# auxboxshield1_42.net
KiCad netlist of a schematic drawn in EAGLE
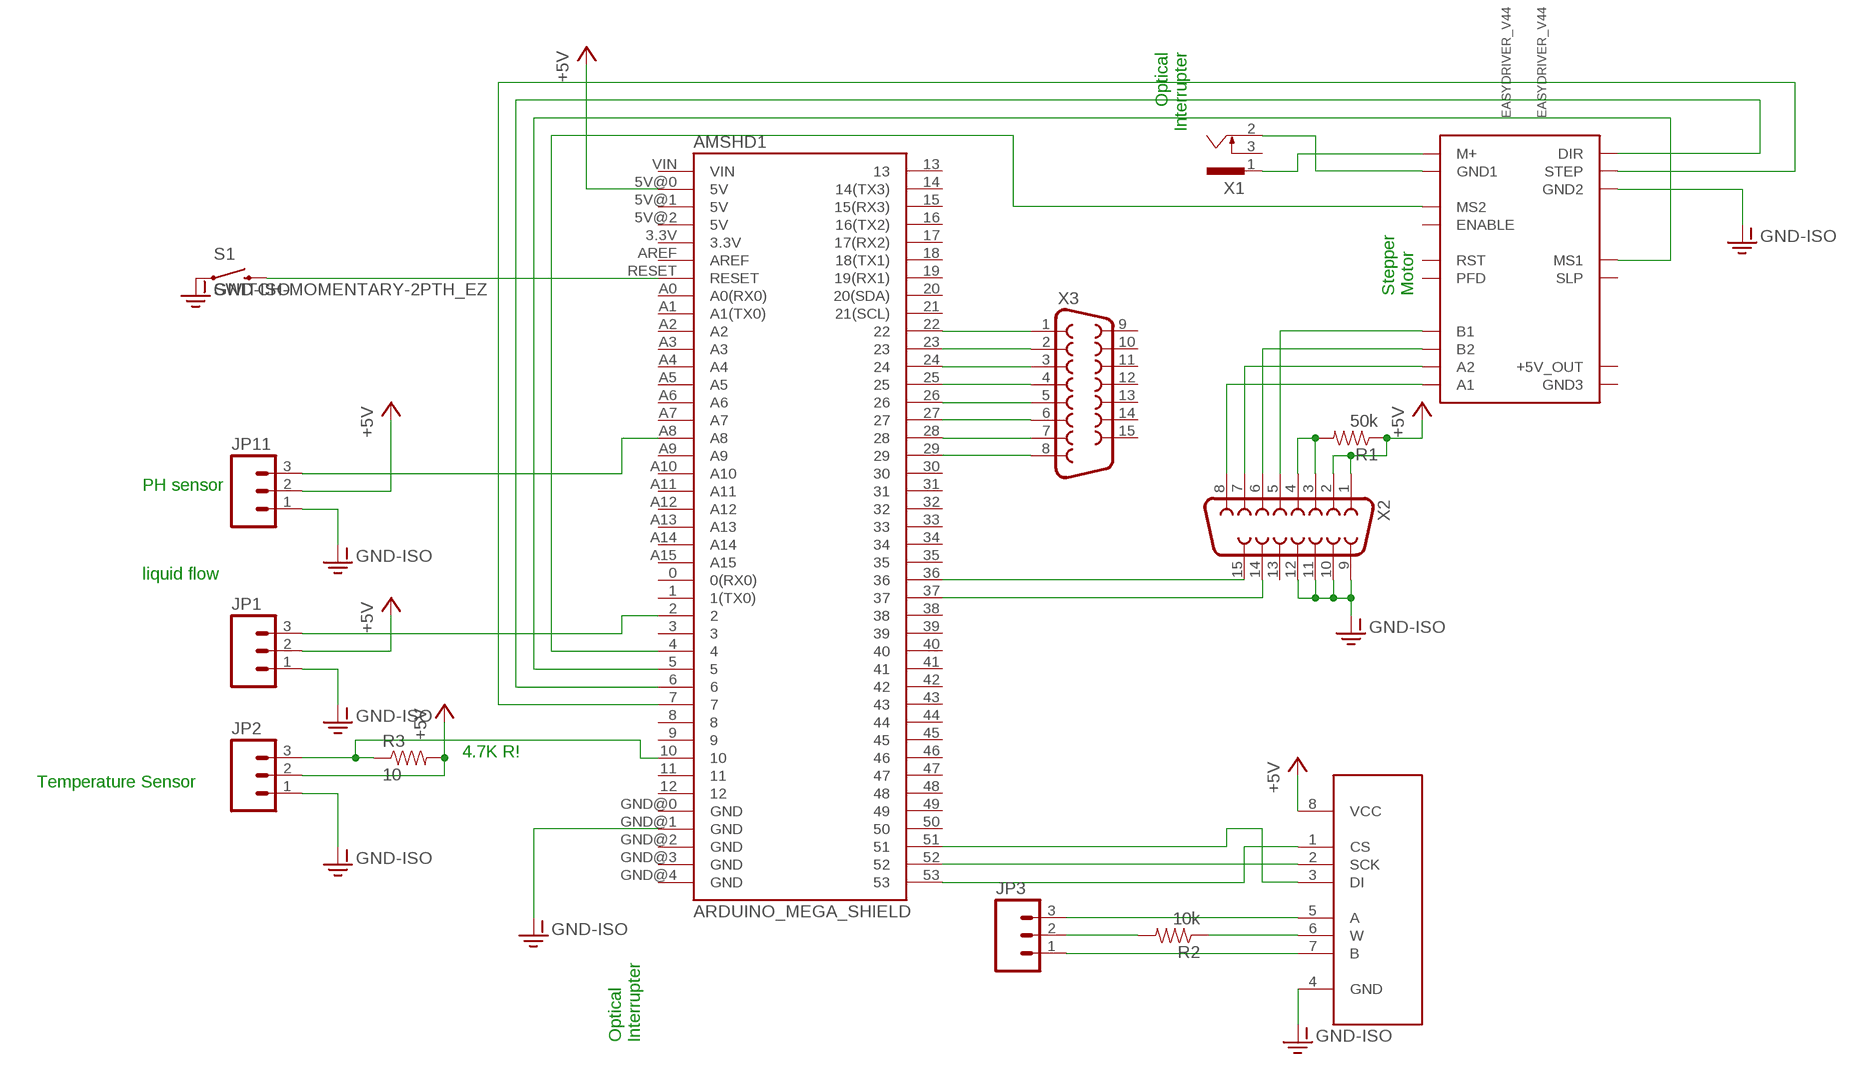
[diagram p0: schematic, sheet 1]

(export (version "E")
  (design (tool "Eeschema 10.0.6"))
  (components
    (comp (ref "AMSHD1")
      (value "ARDUINO_MEGA_SHIELD")
      (footprint "eagle-import:ARDUINO_MEGA_SHIELD")
      (libsource (lib "eagle-import") (part "ARDUINO_MEGA_SHIELD"))
    )
    (comp (ref "EASYDRIVER_V44")
      (value "EASYDRIVER_V44")
      (footprint "eagle-import:EASYDRIVER_V44")
      (libsource (lib "eagle-import") (part "EASYDRIVER_V44"))
    )
    (comp (ref "JP1")
      (value "M03POLAR")
      (footprint "eagle-import:MOLEX-1X3")
      (libsource (lib "eagle-import") (part "M03POLAR"))
    )
    (comp (ref "JP2")
      (value "M03POLAR")
      (footprint "eagle-import:MOLEX-1X3")
      (libsource (lib "eagle-import") (part "M03POLAR"))
    )
    (comp (ref "JP3")
      (value "M03POLAR")
      (footprint "eagle-import:MOLEX-1X3")
      (libsource (lib "eagle-import") (part "M03POLAR"))
    )
    (comp (ref "JP11")
      (value "M03POLAR")
      (footprint "eagle-import:MOLEX-1X3")
      (libsource (lib "eagle-import") (part "M03POLAR"))
    )
    (comp (ref "R1")
      (value "50k")
      (footprint "eagle-import:AXIAL-0.3")
      (libsource (lib "eagle-import") (part "100KOHM-1/4W-5%(PTH)"))
    )
    (comp (ref "R2")
      (value "10k")
      (footprint "eagle-import:AXIAL-0.3")
      (libsource (lib "eagle-import") (part "10KOHM-1/4W-1%(PTH)HORIZ"))
    )
    (comp (ref "R3")
      (value "10")
      (footprint "eagle-import:AXIAL-0.3")
      (libsource (lib "eagle-import") (part "10OHM-1/4W-5%(PTH)"))
    )
    (comp (ref "S1")
      (value "SWITCH-MOMENTARY-2PTH_EZ")
      (footprint "eagle-import:TACTILE-PTH-EZ")
      (libsource (lib "eagle-import") (part "SWITCH-MOMENTARY-2PTH_EZ"))
    )
    (comp (ref "U2")
      (value "MCP41XXXDIL")
      (footprint "eagle-import:DIL-08")
      (libsource (lib "eagle-import") (part "MCP41XXXDIL"))
    )
    (comp (ref "X1")
      (value "SCD-014A")
      (footprint "eagle-import:SCD-014-A")
      (libsource (lib "eagle-import") (part "SCD-014A"))
    )
    (comp (ref "X2")
      (value "F15HP")
      (footprint "eagle-import:F15HP")
      (libsource (lib "eagle-import") (part "F15HP"))
    )
    (comp (ref "X3")
      (value "F15HP")
      (footprint "eagle-import:F15HP")
      (libsource (lib "eagle-import") (part "F15HP"))
    )
  )
  (nets
    (net (code "1") (name "+5V") (class "Default")
      (node (ref "AMSHD1") (pin "5V@0") (pinfunction "5V_5V@0") (pintype "bidirectional"))
      (node (ref "JP1") (pin "2") (pinfunction "2_2") (pintype "passive"))
      (node (ref "JP11") (pin "2") (pinfunction "2_2") (pintype "passive"))
      (node (ref "JP2") (pin "2") (pinfunction "2_2") (pintype "passive"))
      (node (ref "R1") (pin "P$1") (pinfunction "1_P$1") (pintype "passive"))
      (node (ref "R3") (pin "P$2") (pinfunction "2_P$2") (pintype "passive"))
      (node (ref "U2") (pin "8") (pinfunction "VCC_8") (pintype "bidirectional"))
      (node (ref "X2") (pin "1") (pinfunction "1_1") (pintype "passive"))
      (node (ref "X2") (pin "2") (pinfunction "2_2") (pintype "passive"))
    )
    (net (code "2") (name "GND-ISO") (class "Default")
      (node (ref "AMSHD1") (pin "GND@1") (pinfunction "GND_GND@1") (pintype "bidirectional"))
      (node (ref "EASYDRIVER_V44") (pin "GND2") (pinfunction "GND2_GND2") (pintype "bidirectional"))
      (node (ref "JP1") (pin "1") (pinfunction "1_1") (pintype "passive"))
      (node (ref "JP11") (pin "1") (pinfunction "1_1") (pintype "passive"))
      (node (ref "JP2") (pin "1") (pinfunction "1_1") (pintype "passive"))
      (node (ref "S1") (pin "1") (pinfunction "1_1") (pintype "passive"))
      (node (ref "U2") (pin "4") (pinfunction "GND_4") (pintype "bidirectional"))
      (node (ref "X2") (pin "10") (pinfunction "10_10") (pintype "passive"))
      (node (ref "X2") (pin "11") (pinfunction "11_11") (pintype "passive"))
      (node (ref "X2") (pin "12") (pinfunction "12_12") (pintype "passive"))
      (node (ref "X2") (pin "9") (pinfunction "9_9") (pintype "passive"))
    )
    (net (code "3") (name "Net-(AMSHD1-Pad2)") (class "Default")
      (node (ref "AMSHD1") (pin "2") (pinfunction "2_2") (pintype "bidirectional"))
      (node (ref "JP1") (pin "3") (pinfunction "3_3") (pintype "passive"))
    )
    (net (code "4") (name "Net-(AMSHD1-Pad4)") (class "Default")
      (node (ref "AMSHD1") (pin "4") (pinfunction "4_4") (pintype "bidirectional"))
      (node (ref "EASYDRIVER_V44") (pin "MS2") (pinfunction "MS2_MS2") (pintype "bidirectional"))
    )
    (net (code "5") (name "Net-(AMSHD1-Pad5)") (class "Default")
      (node (ref "AMSHD1") (pin "5") (pinfunction "5_5") (pintype "bidirectional"))
      (node (ref "EASYDRIVER_V44") (pin "MS1") (pinfunction "MS1_MS1") (pintype "bidirectional"))
    )
    (net (code "6") (name "Net-(AMSHD1-Pad6)") (class "Default")
      (node (ref "AMSHD1") (pin "6") (pinfunction "6_6") (pintype "bidirectional"))
      (node (ref "EASYDRIVER_V44") (pin "DIR") (pinfunction "DIR_DIR") (pintype "bidirectional"))
    )
    (net (code "7") (name "Net-(AMSHD1-Pad7)") (class "Default")
      (node (ref "AMSHD1") (pin "7") (pinfunction "7_7") (pintype "bidirectional"))
      (node (ref "EASYDRIVER_V44") (pin "STEP") (pinfunction "STEP_STEP") (pintype "bidirectional"))
    )
    (net (code "8") (name "Net-(AMSHD1-Pad22)") (class "Default")
      (node (ref "AMSHD1") (pin "22") (pinfunction "22_22") (pintype "bidirectional"))
      (node (ref "X3") (pin "1") (pinfunction "1_1") (pintype "passive"))
    )
    (net (code "9") (name "Net-(AMSHD1-Pad23)") (class "Default")
      (node (ref "AMSHD1") (pin "23") (pinfunction "23_23") (pintype "bidirectional"))
      (node (ref "X3") (pin "2") (pinfunction "2_2") (pintype "passive"))
    )
    (net (code "10") (name "Net-(AMSHD1-Pad24)") (class "Default")
      (node (ref "AMSHD1") (pin "24") (pinfunction "24_24") (pintype "bidirectional"))
      (node (ref "X3") (pin "3") (pinfunction "3_3") (pintype "passive"))
    )
    (net (code "11") (name "Net-(AMSHD1-Pad25)") (class "Default")
      (node (ref "AMSHD1") (pin "25") (pinfunction "25_25") (pintype "bidirectional"))
      (node (ref "X3") (pin "4") (pinfunction "4_4") (pintype "passive"))
    )
    (net (code "12") (name "Net-(AMSHD1-Pad26)") (class "Default")
      (node (ref "AMSHD1") (pin "26") (pinfunction "26_26") (pintype "bidirectional"))
      (node (ref "X3") (pin "5") (pinfunction "5_5") (pintype "passive"))
    )
    (net (code "13") (name "Net-(AMSHD1-Pad27)") (class "Default")
      (node (ref "AMSHD1") (pin "27") (pinfunction "27_27") (pintype "bidirectional"))
      (node (ref "X3") (pin "6") (pinfunction "6_6") (pintype "passive"))
    )
    (net (code "14") (name "Net-(AMSHD1-Pad28)") (class "Default")
      (node (ref "AMSHD1") (pin "28") (pinfunction "28_28") (pintype "bidirectional"))
      (node (ref "X3") (pin "7") (pinfunction "7_7") (pintype "passive"))
    )
    (net (code "15") (name "Net-(AMSHD1-Pad29)") (class "Default")
      (node (ref "AMSHD1") (pin "29") (pinfunction "29_29") (pintype "bidirectional"))
      (node (ref "X3") (pin "8") (pinfunction "8_8") (pintype "passive"))
    )
    (net (code "16") (name "Net-(AMSHD1-Pad36)") (class "Default")
      (node (ref "AMSHD1") (pin "36") (pinfunction "36_36") (pintype "bidirectional"))
      (node (ref "X2") (pin "15") (pinfunction "15_15") (pintype "passive"))
    )
    (net (code "17") (name "Net-(AMSHD1-Pad37)") (class "Default")
      (node (ref "AMSHD1") (pin "37") (pinfunction "37_37") (pintype "bidirectional"))
      (node (ref "X2") (pin "14") (pinfunction "14_14") (pintype "passive"))
    )
    (net (code "18") (name "Net-(AMSHD1-PadA8)") (class "Default")
      (node (ref "AMSHD1") (pin "A8") (pinfunction "A8_A8") (pintype "bidirectional"))
      (node (ref "JP11") (pin "3") (pinfunction "3_3") (pintype "passive"))
    )
    (net (code "19") (name "Net-(EASYDRIVER_V44-PadA1)") (class "Default")
      (node (ref "EASYDRIVER_V44") (pin "A1") (pinfunction "A1_A1") (pintype "bidirectional"))
      (node (ref "X2") (pin "8") (pinfunction "8_8") (pintype "passive"))
    )
    (net (code "20") (name "Net-(EASYDRIVER_V44-PadA2)") (class "Default")
      (node (ref "EASYDRIVER_V44") (pin "A2") (pinfunction "A2_A2") (pintype "bidirectional"))
      (node (ref "X2") (pin "7") (pinfunction "7_7") (pintype "passive"))
    )
    (net (code "21") (name "Net-(EASYDRIVER_V44-PadB1)") (class "Default")
      (node (ref "EASYDRIVER_V44") (pin "B1") (pinfunction "B1_B1") (pintype "bidirectional"))
      (node (ref "X2") (pin "5") (pinfunction "5_5") (pintype "passive"))
    )
    (net (code "22") (name "Net-(EASYDRIVER_V44-PadB2)") (class "Default")
      (node (ref "EASYDRIVER_V44") (pin "B2") (pinfunction "B2_B2") (pintype "bidirectional"))
      (node (ref "X2") (pin "6") (pinfunction "6_6") (pintype "passive"))
    )
    (net (code "23") (name "Net-(EASYDRIVER_V44-PadGND1)") (class "Default")
      (node (ref "EASYDRIVER_V44") (pin "GND1") (pinfunction "GND1_GND1") (pintype "bidirectional"))
      (node (ref "X1") (pin "2") (pinfunction "2_2") (pintype "passive"))
    )
    (net (code "24") (name "Net-(EASYDRIVER_V44-PadM+)") (class "Default")
      (node (ref "EASYDRIVER_V44") (pin "M+") (pinfunction "M+_M+") (pintype "bidirectional"))
      (node (ref "X1") (pin "1") (pinfunction "1_1") (pintype "passive"))
    )
    (net (code "25") (name "Net-(R1-2)") (class "Default")
      (node (ref "R1") (pin "P$2") (pinfunction "2_P$2") (pintype "passive"))
      (node (ref "X2") (pin "3") (pinfunction "3_3") (pintype "passive"))
      (node (ref "X2") (pin "4") (pinfunction "4_4") (pintype "passive"))
    )
    (net (code "26") (name "Net-(R2-1)") (class "Default")
      (node (ref "R2") (pin "P$1") (pinfunction "1_P$1") (pintype "passive"))
      (node (ref "U2") (pin "6") (pinfunction "W_6") (pintype "bidirectional"))
    )
    (net (code "27") (name "Net-(R2-2)") (class "Default")
      (node (ref "JP3") (pin "2") (pinfunction "2_2") (pintype "passive"))
      (node (ref "R2") (pin "P$2") (pinfunction "2_P$2") (pintype "passive"))
    )
    (net (code "28") (name "Net-(R3-1)") (class "Default")
      (node (ref "AMSHD1") (pin "10") (pinfunction "10_10") (pintype "bidirectional"))
      (node (ref "JP2") (pin "3") (pinfunction "3_3") (pintype "passive"))
      (node (ref "R3") (pin "P$1") (pinfunction "1_P$1") (pintype "passive"))
    )
    (net (code "29") (name "Net-(S1-2)") (class "Default")
      (node (ref "AMSHD1") (pin "RESET") (pinfunction "RESET_RESET") (pintype "bidirectional"))
      (node (ref "S1") (pin "3") (pinfunction "2_3") (pintype "passive"))
    )
    (net (code "30") (name "Net-(U2-A)") (class "Default")
      (node (ref "JP3") (pin "3") (pinfunction "3_3") (pintype "passive"))
      (node (ref "U2") (pin "5") (pinfunction "A_5") (pintype "bidirectional"))
    )
    (net (code "31") (name "Net-(U2-B)") (class "Default")
      (node (ref "JP3") (pin "1") (pinfunction "1_1") (pintype "passive"))
      (node (ref "U2") (pin "7") (pinfunction "B_7") (pintype "bidirectional"))
    )
    (net (code "32") (name "Net-(U2-CS)") (class "Default")
      (node (ref "AMSHD1") (pin "53") (pinfunction "53_53") (pintype "bidirectional"))
      (node (ref "U2") (pin "1") (pinfunction "CS_1") (pintype "bidirectional"))
    )
    (net (code "33") (name "Net-(U2-DI)") (class "Default")
      (node (ref "AMSHD1") (pin "51") (pinfunction "51_51") (pintype "bidirectional"))
      (node (ref "U2") (pin "3") (pinfunction "DI_3") (pintype "bidirectional"))
    )
    (net (code "34") (name "Net-(U2-SCK)") (class "Default")
      (node (ref "AMSHD1") (pin "52") (pinfunction "52_52") (pintype "bidirectional"))
      (node (ref "U2") (pin "2") (pinfunction "SCK_2") (pintype "bidirectional"))
    )
    (net (code "35") (name "unconnected-(AMSHD1-0(RX0)-Pad0)") (class "Default")
      (node (ref "AMSHD1") (pin "0") (pinfunction "0(RX0)_0") (pintype "bidirectional"))
    )
    (net (code "36") (name "unconnected-(AMSHD1-1(TX0)-Pad1)") (class "Default")
      (node (ref "AMSHD1") (pin "1") (pinfunction "1(TX0)_1") (pintype "bidirectional"))
    )
    (net (code "37") (name "unconnected-(AMSHD1-5V-Pad5V@1)") (class "Default")
      (node (ref "AMSHD1") (pin "5V@1") (pinfunction "5V_5V@1") (pintype "bidirectional"))
    )
    (net (code "38") (name "unconnected-(AMSHD1-5V-Pad5V@2)") (class "Default")
      (node (ref "AMSHD1") (pin "5V@2") (pinfunction "5V_5V@2") (pintype "bidirectional"))
    )
    (net (code "39") (name "unconnected-(AMSHD1-14(TX3)-Pad14)") (class "Default")
      (node (ref "AMSHD1") (pin "14") (pinfunction "14(TX3)_14") (pintype "bidirectional"))
    )
    (net (code "40") (name "unconnected-(AMSHD1-15(RX3)-Pad15)") (class "Default")
      (node (ref "AMSHD1") (pin "15") (pinfunction "15(RX3)_15") (pintype "bidirectional"))
    )
    (net (code "41") (name "unconnected-(AMSHD1-16(TX2)-Pad16)") (class "Default")
      (node (ref "AMSHD1") (pin "16") (pinfunction "16(TX2)_16") (pintype "bidirectional"))
    )
    (net (code "42") (name "unconnected-(AMSHD1-17(RX2)-Pad17)") (class "Default")
      (node (ref "AMSHD1") (pin "17") (pinfunction "17(RX2)_17") (pintype "bidirectional"))
    )
    (net (code "43") (name "unconnected-(AMSHD1-18(TX1)-Pad18)") (class "Default")
      (node (ref "AMSHD1") (pin "18") (pinfunction "18(TX1)_18") (pintype "bidirectional"))
    )
    (net (code "44") (name "unconnected-(AMSHD1-19(RX1)-Pad19)") (class "Default")
      (node (ref "AMSHD1") (pin "19") (pinfunction "19(RX1)_19") (pintype "bidirectional"))
    )
    (net (code "45") (name "unconnected-(AMSHD1-20(SDA)-Pad20)") (class "Default")
      (node (ref "AMSHD1") (pin "20") (pinfunction "20(SDA)_20") (pintype "bidirectional"))
    )
    (net (code "46") (name "unconnected-(AMSHD1-21(SCL)-Pad21)") (class "Default")
      (node (ref "AMSHD1") (pin "21") (pinfunction "21(SCL)_21") (pintype "bidirectional"))
    )
    (net (code "47") (name "unconnected-(AMSHD1-A0(RX0)-PadA0)") (class "Default")
      (node (ref "AMSHD1") (pin "A0") (pinfunction "A0(RX0)_A0") (pintype "bidirectional"))
    )
    (net (code "48") (name "unconnected-(AMSHD1-A1(TX0)-PadA1)") (class "Default")
      (node (ref "AMSHD1") (pin "A1") (pinfunction "A1(TX0)_A1") (pintype "bidirectional"))
    )
    (net (code "49") (name "unconnected-(AMSHD1-GND-PadGND@0)") (class "Default")
      (node (ref "AMSHD1") (pin "GND@0") (pinfunction "GND_GND@0") (pintype "bidirectional"))
    )
    (net (code "50") (name "unconnected-(AMSHD1-GND-PadGND@2)") (class "Default")
      (node (ref "AMSHD1") (pin "GND@2") (pinfunction "GND_GND@2") (pintype "bidirectional"))
    )
    (net (code "51") (name "unconnected-(AMSHD1-GND-PadGND@3)") (class "Default")
      (node (ref "AMSHD1") (pin "GND@3") (pinfunction "GND_GND@3") (pintype "bidirectional"))
    )
    (net (code "52") (name "unconnected-(AMSHD1-GND-PadGND@4)") (class "Default")
      (node (ref "AMSHD1") (pin "GND@4") (pinfunction "GND_GND@4") (pintype "bidirectional"))
    )
    (net (code "53") (name "unconnected-(AMSHD1-Pad3)") (class "Default")
      (node (ref "AMSHD1") (pin "3") (pinfunction "3_3") (pintype "bidirectional"))
    )
    (net (code "54") (name "unconnected-(AMSHD1-Pad3.3V)") (class "Default")
      (node (ref "AMSHD1") (pin "3.3V") (pinfunction "3.3V_3.3V") (pintype "bidirectional"))
    )
    (net (code "55") (name "unconnected-(AMSHD1-Pad8)") (class "Default")
      (node (ref "AMSHD1") (pin "8") (pinfunction "8_8") (pintype "bidirectional"))
    )
    (net (code "56") (name "unconnected-(AMSHD1-Pad9)") (class "Default")
      (node (ref "AMSHD1") (pin "9") (pinfunction "9_9") (pintype "bidirectional"))
    )
    (net (code "57") (name "unconnected-(AMSHD1-Pad11)") (class "Default")
      (node (ref "AMSHD1") (pin "11") (pinfunction "11_11") (pintype "bidirectional"))
    )
    (net (code "58") (name "unconnected-(AMSHD1-Pad12)") (class "Default")
      (node (ref "AMSHD1") (pin "12") (pinfunction "12_12") (pintype "bidirectional"))
    )
    (net (code "59") (name "unconnected-(AMSHD1-Pad13)") (class "Default")
      (node (ref "AMSHD1") (pin "13") (pinfunction "13_13") (pintype "bidirectional"))
    )
    (net (code "60") (name "unconnected-(AMSHD1-Pad30)") (class "Default")
      (node (ref "AMSHD1") (pin "30") (pinfunction "30_30") (pintype "bidirectional"))
    )
    (net (code "61") (name "unconnected-(AMSHD1-Pad31)") (class "Default")
      (node (ref "AMSHD1") (pin "31") (pinfunction "31_31") (pintype "bidirectional"))
    )
    (net (code "62") (name "unconnected-(AMSHD1-Pad32)") (class "Default")
      (node (ref "AMSHD1") (pin "32") (pinfunction "32_32") (pintype "bidirectional"))
    )
    (net (code "63") (name "unconnected-(AMSHD1-Pad33)") (class "Default")
      (node (ref "AMSHD1") (pin "33") (pinfunction "33_33") (pintype "bidirectional"))
    )
    (net (code "64") (name "unconnected-(AMSHD1-Pad34)") (class "Default")
      (node (ref "AMSHD1") (pin "34") (pinfunction "34_34") (pintype "bidirectional"))
    )
    (net (code "65") (name "unconnected-(AMSHD1-Pad35)") (class "Default")
      (node (ref "AMSHD1") (pin "35") (pinfunction "35_35") (pintype "bidirectional"))
    )
    (net (code "66") (name "unconnected-(AMSHD1-Pad38)") (class "Default")
      (node (ref "AMSHD1") (pin "38") (pinfunction "38_38") (pintype "bidirectional"))
    )
    (net (code "67") (name "unconnected-(AMSHD1-Pad39)") (class "Default")
      (node (ref "AMSHD1") (pin "39") (pinfunction "39_39") (pintype "bidirectional"))
    )
    (net (code "68") (name "unconnected-(AMSHD1-Pad40)") (class "Default")
      (node (ref "AMSHD1") (pin "40") (pinfunction "40_40") (pintype "bidirectional"))
    )
    (net (code "69") (name "unconnected-(AMSHD1-Pad41)") (class "Default")
      (node (ref "AMSHD1") (pin "41") (pinfunction "41_41") (pintype "bidirectional"))
    )
    (net (code "70") (name "unconnected-(AMSHD1-Pad42)") (class "Default")
      (node (ref "AMSHD1") (pin "42") (pinfunction "42_42") (pintype "bidirectional"))
    )
    (net (code "71") (name "unconnected-(AMSHD1-Pad43)") (class "Default")
      (node (ref "AMSHD1") (pin "43") (pinfunction "43_43") (pintype "bidirectional"))
    )
    (net (code "72") (name "unconnected-(AMSHD1-Pad44)") (class "Default")
      (node (ref "AMSHD1") (pin "44") (pinfunction "44_44") (pintype "bidirectional"))
    )
    (net (code "73") (name "unconnected-(AMSHD1-Pad45)") (class "Default")
      (node (ref "AMSHD1") (pin "45") (pinfunction "45_45") (pintype "bidirectional"))
    )
    (net (code "74") (name "unconnected-(AMSHD1-Pad46)") (class "Default")
      (node (ref "AMSHD1") (pin "46") (pinfunction "46_46") (pintype "bidirectional"))
    )
    (net (code "75") (name "unconnected-(AMSHD1-Pad47)") (class "Default")
      (node (ref "AMSHD1") (pin "47") (pinfunction "47_47") (pintype "bidirectional"))
    )
    (net (code "76") (name "unconnected-(AMSHD1-Pad48)") (class "Default")
      (node (ref "AMSHD1") (pin "48") (pinfunction "48_48") (pintype "bidirectional"))
    )
    (net (code "77") (name "unconnected-(AMSHD1-Pad49)") (class "Default")
      (node (ref "AMSHD1") (pin "49") (pinfunction "49_49") (pintype "bidirectional"))
    )
    (net (code "78") (name "unconnected-(AMSHD1-Pad50)") (class "Default")
      (node (ref "AMSHD1") (pin "50") (pinfunction "50_50") (pintype "bidirectional"))
    )
    (net (code "79") (name "unconnected-(AMSHD1-PadA2)") (class "Default")
      (node (ref "AMSHD1") (pin "A2") (pinfunction "A2_A2") (pintype "bidirectional"))
    )
    (net (code "80") (name "unconnected-(AMSHD1-PadA3)") (class "Default")
      (node (ref "AMSHD1") (pin "A3") (pinfunction "A3_A3") (pintype "bidirectional"))
    )
    (net (code "81") (name "unconnected-(AMSHD1-PadA4)") (class "Default")
      (node (ref "AMSHD1") (pin "A4") (pinfunction "A4_A4") (pintype "bidirectional"))
    )
    (net (code "82") (name "unconnected-(AMSHD1-PadA5)") (class "Default")
      (node (ref "AMSHD1") (pin "A5") (pinfunction "A5_A5") (pintype "bidirectional"))
    )
    (net (code "83") (name "unconnected-(AMSHD1-PadA6)") (class "Default")
      (node (ref "AMSHD1") (pin "A6") (pinfunction "A6_A6") (pintype "bidirectional"))
    )
    (net (code "84") (name "unconnected-(AMSHD1-PadA7)") (class "Default")
      (node (ref "AMSHD1") (pin "A7") (pinfunction "A7_A7") (pintype "bidirectional"))
    )
    (net (code "85") (name "unconnected-(AMSHD1-PadA9)") (class "Default")
      (node (ref "AMSHD1") (pin "A9") (pinfunction "A9_A9") (pintype "bidirectional"))
    )
    (net (code "86") (name "unconnected-(AMSHD1-PadA10)") (class "Default")
      (node (ref "AMSHD1") (pin "A10") (pinfunction "A10_A10") (pintype "bidirectional"))
    )
    (net (code "87") (name "unconnected-(AMSHD1-PadA11)") (class "Default")
      (node (ref "AMSHD1") (pin "A11") (pinfunction "A11_A11") (pintype "bidirectional"))
    )
    (net (code "88") (name "unconnected-(AMSHD1-PadA12)") (class "Default")
      (node (ref "AMSHD1") (pin "A12") (pinfunction "A12_A12") (pintype "bidirectional"))
    )
    (net (code "89") (name "unconnected-(AMSHD1-PadA13)") (class "Default")
      (node (ref "AMSHD1") (pin "A13") (pinfunction "A13_A13") (pintype "bidirectional"))
    )
    (net (code "90") (name "unconnected-(AMSHD1-PadA14)") (class "Default")
      (node (ref "AMSHD1") (pin "A14") (pinfunction "A14_A14") (pintype "bidirectional"))
    )
    (net (code "91") (name "unconnected-(AMSHD1-PadA15)") (class "Default")
      (node (ref "AMSHD1") (pin "A15") (pinfunction "A15_A15") (pintype "bidirectional"))
    )
    (net (code "92") (name "unconnected-(AMSHD1-PadAREF)") (class "Default")
      (node (ref "AMSHD1") (pin "AREF") (pinfunction "AREF_AREF") (pintype "bidirectional"))
    )
    (net (code "93") (name "unconnected-(AMSHD1-PadVIN)") (class "Default")
      (node (ref "AMSHD1") (pin "VIN") (pinfunction "VIN_VIN") (pintype "bidirectional"))
    )
    (net (code "94") (name "unconnected-(EASYDRIVER_V44-+5V_OUT-PadP$11)") (class "Default")
      (node (ref "EASYDRIVER_V44") (pin "P$11") (pinfunction "+5V_OUT_P$11") (pintype "bidirectional"))
    )
    (net (code "95") (name "unconnected-(EASYDRIVER_V44-PadENABLE)") (class "Default")
      (node (ref "EASYDRIVER_V44") (pin "ENABLE") (pinfunction "ENABLE_ENABLE") (pintype "bidirectional"))
    )
    (net (code "96") (name "unconnected-(EASYDRIVER_V44-PadGND3)") (class "Default")
      (node (ref "EASYDRIVER_V44") (pin "GND3") (pinfunction "GND3_GND3") (pintype "bidirectional"))
    )
    (net (code "97") (name "unconnected-(EASYDRIVER_V44-PadPFD)") (class "Default")
      (node (ref "EASYDRIVER_V44") (pin "PFD") (pinfunction "PFD_PFD") (pintype "bidirectional"))
    )
    (net (code "98") (name "unconnected-(EASYDRIVER_V44-PadRST)") (class "Default")
      (node (ref "EASYDRIVER_V44") (pin "RST") (pinfunction "RST_RST") (pintype "bidirectional"))
    )
    (net (code "99") (name "unconnected-(EASYDRIVER_V44-SLP-PadSLEEP)") (class "Default")
      (node (ref "EASYDRIVER_V44") (pin "SLEEP") (pinfunction "SLP_SLEEP") (pintype "bidirectional"))
    )
    (net (code "100") (name "unconnected-(X1-Pad3)") (class "Default")
      (node (ref "X1") (pin "3") (pinfunction "3_3") (pintype "passive"))
    )
    (net (code "101") (name "unconnected-(X2-Pad13)") (class "Default")
      (node (ref "X2") (pin "13") (pinfunction "13_13") (pintype "passive"))
    )
    (net (code "102") (name "unconnected-(X3-Pad9)") (class "Default")
      (node (ref "X3") (pin "9") (pinfunction "9_9") (pintype "passive"))
    )
    (net (code "103") (name "unconnected-(X3-Pad10)") (class "Default")
      (node (ref "X3") (pin "10") (pinfunction "10_10") (pintype "passive"))
    )
    (net (code "104") (name "unconnected-(X3-Pad11)") (class "Default")
      (node (ref "X3") (pin "11") (pinfunction "11_11") (pintype "passive"))
    )
    (net (code "105") (name "unconnected-(X3-Pad12)") (class "Default")
      (node (ref "X3") (pin "12") (pinfunction "12_12") (pintype "passive"))
    )
    (net (code "106") (name "unconnected-(X3-Pad13)") (class "Default")
      (node (ref "X3") (pin "13") (pinfunction "13_13") (pintype "passive"))
    )
    (net (code "107") (name "unconnected-(X3-Pad14)") (class "Default")
      (node (ref "X3") (pin "14") (pinfunction "14_14") (pintype "passive"))
    )
    (net (code "108") (name "unconnected-(X3-Pad15)") (class "Default")
      (node (ref "X3") (pin "15") (pinfunction "15_15") (pintype "passive"))
    )
  )
)
